# AFBR-TX-fiber_optic_transmiter.net
KiCad netlist of a schematic drawn in Altium Designer
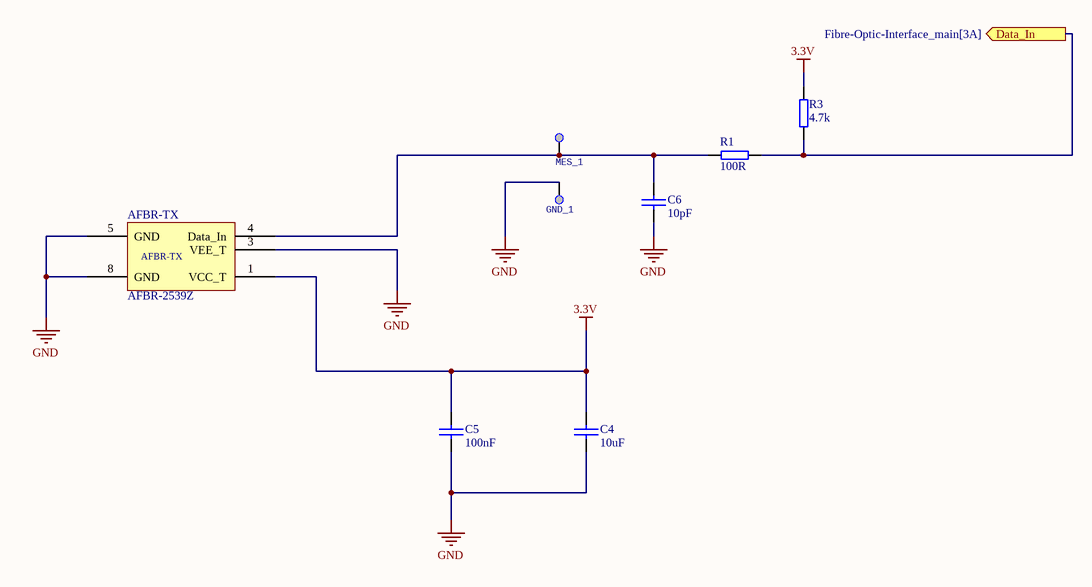
[diagram p0: AFBR-TX-fiber_optic_transmiter.SchDoc]

(export (version "E")
  (design (tool "Eeschema 10.0.6"))
  (components
    (comp (ref "AFBR-TX")
      (value "AFBR-2539Z")
      (footprint "AFBR-TX/RX-HORIZONTAL")
      (description "Fiber Optic Transmitters, Receivers, Transceivers VL V 50MBd RX inv")
      (libsource (lib "fibre_optic_transmiters") (part "AFBR-TX"))
    )
    (comp (ref "C4")
      (value "10uF")
      (footprint "1206")
      (description "Capacitor")
      (libsource (lib "passive_elements") (part "C_1"))
    )
    (comp (ref "C5")
      (value "100nF")
      (footprint "0603C")
      (description "Capacitor")
      (libsource (lib "passive_elements") (part "C"))
    )
    (comp (ref "C6")
      (value "10pF")
      (footprint "0603C")
      (description "Capacitor")
      (libsource (lib "passive_elements") (part "C_3"))
    )
    (comp (ref "GND_1")
      (value "PK_1")
      (footprint "PK")
      (description "Punkt")
      (libsource (lib "others") (part "PK_1"))
    )
    (comp (ref "MES_1")
      (value "PK_1")
      (footprint "PK")
      (description "Punkt")
      (libsource (lib "others") (part "PK_1"))
    )
    (comp (ref "R1") (value "100R") (footprint "0603R") (libsource (lib "passive_elements") (part "R_1")))
    (comp (ref "R3") (value "4.7k") (footprint "0603R") (libsource (lib "passive_elements") (part "R")))
  )
  (nets
    (net (code "1") (name "/Data_In") (class "Default")
      (node (ref "R1") (pin "2") (pinfunction "2_2") (pintype "passive"))
      (node (ref "R3") (pin "1") (pinfunction "1_1") (pintype "passive"))
    )
    (net (code "2") (name "3.3V") (class "Default")
      (node (ref "AFBR-TX") (pin "1") (pinfunction "VCC_T_1") (pintype "passive"))
      (node (ref "C4") (pin "1") (pinfunction "1_1") (pintype "passive"))
      (node (ref "C5") (pin "1") (pinfunction "1_1") (pintype "passive"))
      (node (ref "R3") (pin "2") (pinfunction "2_2") (pintype "passive"))
    )
    (net (code "3") (name "GND") (class "Default")
      (node (ref "AFBR-TX") (pin "3") (pinfunction "VEE_T_3") (pintype "passive"))
      (node (ref "AFBR-TX") (pin "5") (pinfunction "GND_5") (pintype "passive"))
      (node (ref "AFBR-TX") (pin "8") (pinfunction "GND_8") (pintype "passive"))
      (node (ref "C4") (pin "2") (pinfunction "2_2") (pintype "passive"))
      (node (ref "C5") (pin "2") (pinfunction "2_2") (pintype "passive"))
      (node (ref "C6") (pin "2") (pinfunction "2_2") (pintype "passive"))
      (node (ref "GND_1") (pin "1") (pinfunction "1_1") (pintype "passive"))
    )
    (net (code "4") (name "Net-(AFBR-TX-Data_In)") (class "Default")
      (node (ref "AFBR-TX") (pin "4") (pinfunction "Data_In_4") (pintype "passive"))
      (node (ref "C6") (pin "1") (pinfunction "1_1") (pintype "passive"))
      (node (ref "MES_1") (pin "1") (pinfunction "1_1") (pintype "passive"))
      (node (ref "R1") (pin "1") (pinfunction "1_1") (pintype "passive"))
    )
  )
)
